# 1_ROV_Filter.net
KiCad netlist of a schematic drawn in Altium Designer
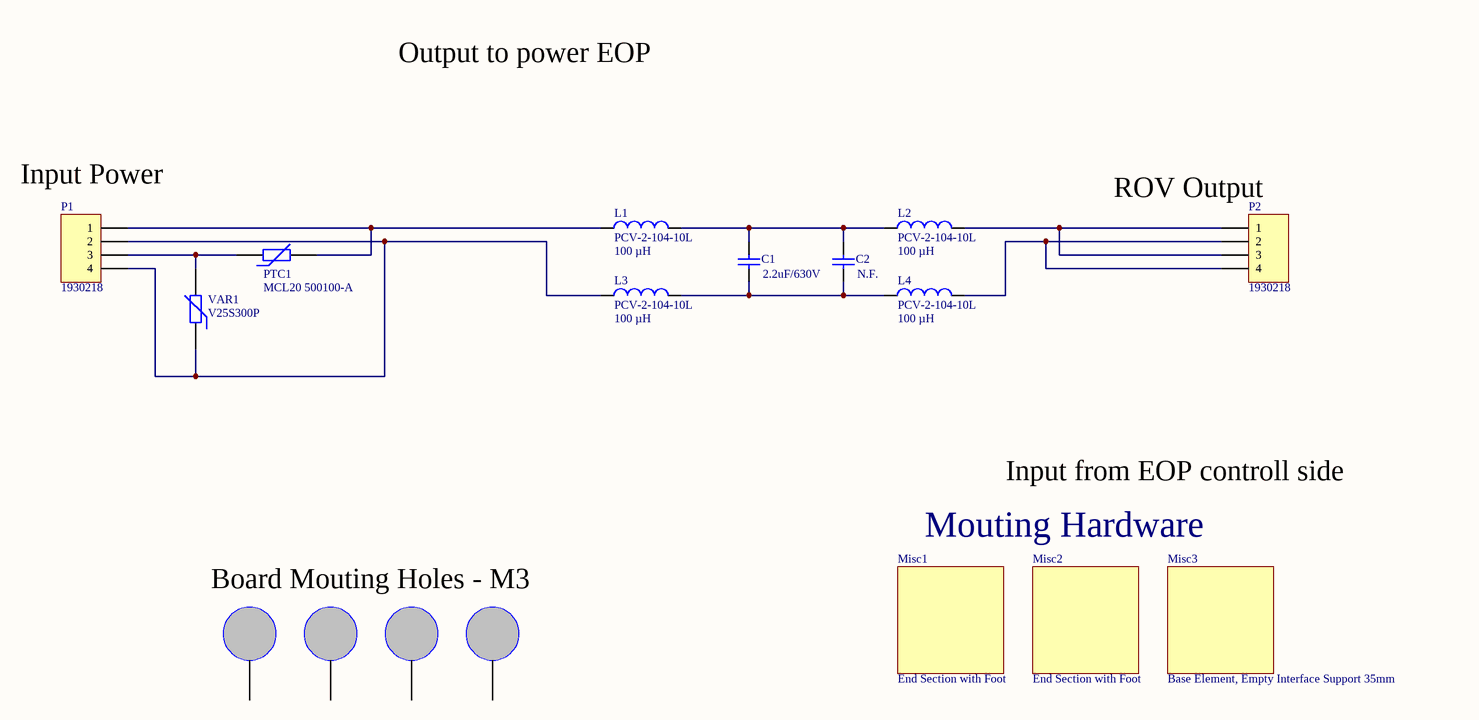
[diagram p0: [1]ROV_Filter.SchDoc]

(export (version "E")
  (design (tool "Eeschema 10.0.6"))
  (components
    (comp (ref "C1")
      (value "2.2uF/630V")
      (footprint "ECWFD Cap Straight Type")
      (description "Capacitor")
      (fields (field (name "Comment") "0603") (field (name "PUBLISHER") "Altium Limited"))
      (libsource (lib "Miscellaneous Devices") (part "Cap"))
    )
    (comp (ref "C2")
      (value "N.F.")
      (footprint "ECWFD Cap Straight Type")
      (description "Capacitor")
      (fields (field (name "Comment") "0603") (field (name "PUBLISHER") "Altium Limited"))
      (libsource (lib "Miscellaneous Devices") (part "Cap"))
    )
    (comp (ref "L1")
      (value "PCV-2-104-10L")
      (footprint "PCV-2")
      (description "Inductor")
      (fields (field (name "ALTIUM_VALUE") "100 µH") (field (name "PUBLISHER") "Altium Limited"))
      (libsource (lib "Miscellaneous Devices") (part "Inductor"))
    )
    (comp (ref "L2")
      (value "PCV-2-104-10L")
      (footprint "PCV-2")
      (description "Inductor")
      (fields (field (name "ALTIUM_VALUE") "100 µH") (field (name "PUBLISHER") "Altium Limited"))
      (libsource (lib "Miscellaneous Devices") (part "Inductor"))
    )
    (comp (ref "L3")
      (value "PCV-2-104-10L")
      (footprint "PCV-2")
      (description "Inductor")
      (fields (field (name "ALTIUM_VALUE") "100 µH") (field (name "PUBLISHER") "Altium Limited"))
      (libsource (lib "Miscellaneous Devices") (part "Inductor"))
    )
    (comp (ref "L4")
      (value "PCV-2-104-10L")
      (footprint "PCV-2")
      (description "Inductor")
      (fields (field (name "ALTIUM_VALUE") "100 µH") (field (name "PUBLISHER") "Altium Limited"))
      (libsource (lib "Miscellaneous Devices") (part "Inductor"))
    )
    (comp (ref "MH1")
      (value "Mouting Hole")
      (footprint "M3 Mounting Hole")
      (libsource (lib "custom_components") (part "Mouting Hole"))
    )
    (comp (ref "MH2")
      (value "Mouting Hole")
      (footprint "M3 Mounting Hole")
      (libsource (lib "custom_components") (part "Mouting Hole"))
    )
    (comp (ref "MH3")
      (value "Mouting Hole")
      (footprint "M3 Mounting Hole")
      (libsource (lib "custom_components") (part "Mouting Hole"))
    )
    (comp (ref "MH4")
      (value "Mouting Hole")
      (footprint "M3 Mounting Hole")
      (libsource (lib "custom_components") (part "Mouting Hole"))
    )
    (comp (ref "Misc1")
      (value "End Section with Foot")
      (fields (field (name "MANUFACTURER PART NO.") "CIME/E/SEF1000S"))
      (libsource (lib "custom_components") (part "Empty Component"))
    )
    (comp (ref "Misc2")
      (value "End Section with Foot")
      (fields (field (name "MANUFACTURER PART NO.") "CIME/E/SEF1000S"))
      (libsource (lib "custom_components") (part "Empty Component"))
    )
    (comp (ref "Misc3")
      (value "Base Element, Empty Interface Support 35mm")
      (fields (field (name "MANUFACTURER PART NO.") "CIME/E/BE3500S"))
      (libsource (lib "custom_components") (part "Empty Component"))
    )
    (comp (ref "P1")
      (value "1930218")
      (footprint "Phoenix Contact 1930218")
      (description "Header, 4-Pin")
      (fields (field (name "PUBLISHER") "Altium Limited"))
      (libsource (lib "") (part "Header 4_1"))
    )
    (comp (ref "P2")
      (value "1930218")
      (footprint "Phoenix Contact 1930218 REVERSED")
      (description "Header, 4-Pin")
      (fields (field (name "PUBLISHER") "Altium Limited"))
      (libsource (lib "Miscellaneous Connectors") (part "Header 4"))
    )
    (comp (ref "PTC1")
      (value "MCL20 500100-A")
      (footprint "MCL20 PTC")
      (description "Varistor (Voltage-Sensitive Resistor)")
      (fields (field (name "PUBLISHER") "Altium Limited"))
      (libsource (lib "Miscellaneous Devices") (part "Res Varistor"))
    )
    (comp (ref "VAR1")
      (value "V25S300P")
      (footprint "UltraMOV 25S Varistor Series")
      (description "Varistor (Voltage-Sensitive Resistor)")
      (fields (field (name "PUBLISHER") "Altium Limited"))
      (libsource (lib "Miscellaneous Devices") (part "Res Varistor"))
    )
  )
  (nets
    (net (code "1") (name "Net-(C1-Pad1)") (class "Default")
      (node (ref "C1") (pin "1") (pinfunction "1_1") (pintype "passive"))
      (node (ref "C2") (pin "1") (pinfunction "1_1") (pintype "passive"))
      (node (ref "L3") (pin "2") (pinfunction "2_2") (pintype "passive"))
      (node (ref "L4") (pin "1") (pinfunction "1_1") (pintype "passive"))
    )
    (net (code "2") (name "Net-(C1-Pad2)") (class "Default")
      (node (ref "C1") (pin "2") (pinfunction "2_2") (pintype "passive"))
      (node (ref "C2") (pin "2") (pinfunction "2_2") (pintype "passive"))
      (node (ref "L1") (pin "2") (pinfunction "2_2") (pintype "passive"))
      (node (ref "L2") (pin "1") (pinfunction "1_1") (pintype "passive"))
    )
    (net (code "3") (name "Net-(L1-Pad1)") (class "Default")
      (node (ref "L1") (pin "1") (pinfunction "1_1") (pintype "passive"))
      (node (ref "P1") (pin "1") (pinfunction "1_1") (pintype "passive"))
      (node (ref "PTC1") (pin "2") (pinfunction "2_2") (pintype "passive"))
    )
    (net (code "4") (name "Net-(L2-Pad2)") (class "Default")
      (node (ref "L2") (pin "2") (pinfunction "2_2") (pintype "passive"))
      (node (ref "P2") (pin "1") (pinfunction "1_1") (pintype "passive"))
      (node (ref "P2") (pin "3") (pinfunction "3_3") (pintype "passive"))
    )
    (net (code "5") (name "Net-(L3-Pad1)") (class "Default")
      (node (ref "L3") (pin "1") (pinfunction "1_1") (pintype "passive"))
      (node (ref "P1") (pin "2") (pinfunction "2_2") (pintype "passive"))
      (node (ref "P1") (pin "4") (pinfunction "4_4") (pintype "passive"))
      (node (ref "VAR1") (pin "1") (pinfunction "1_1") (pintype "passive"))
    )
    (net (code "6") (name "Net-(L4-Pad2)") (class "Default")
      (node (ref "L4") (pin "2") (pinfunction "2_2") (pintype "passive"))
      (node (ref "P2") (pin "2") (pinfunction "2_2") (pintype "passive"))
      (node (ref "P2") (pin "4") (pinfunction "4_4") (pintype "passive"))
    )
    (net (code "7") (name "Net-(P1-Pad3)") (class "Default")
      (node (ref "P1") (pin "3") (pinfunction "3_3") (pintype "passive"))
      (node (ref "PTC1") (pin "1") (pinfunction "1_1") (pintype "passive"))
      (node (ref "VAR1") (pin "2") (pinfunction "2_2") (pintype "passive"))
    )
    (net (code "8") (name "unconnected-(MH1-Pad1)") (class "Default")
      (node (ref "MH1") (pin "1") (pinfunction "1_1") (pintype "passive"))
    )
    (net (code "9") (name "unconnected-(MH2-Pad1)") (class "Default")
      (node (ref "MH2") (pin "1") (pinfunction "1_1") (pintype "passive"))
    )
    (net (code "10") (name "unconnected-(MH3-Pad1)") (class "Default")
      (node (ref "MH3") (pin "1") (pinfunction "1_1") (pintype "passive"))
    )
    (net (code "11") (name "unconnected-(MH4-Pad1)") (class "Default")
      (node (ref "MH4") (pin "1") (pinfunction "1_1") (pintype "passive"))
    )
  )
)
